# phase_sense.net
KiCad netlist of a schematic drawn in Altium Designer
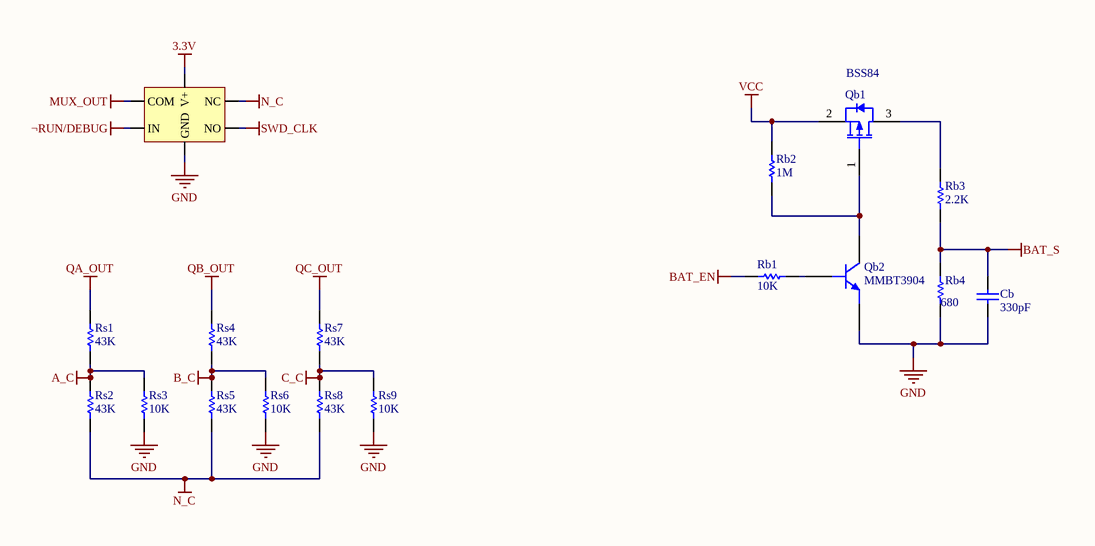
[diagram p0: phase_sense.SchDoc]

(export (version "E")
  (design (tool "Eeschema 10.0.6"))
  (components
    (comp (ref "Cb")
      (value "330pF")
      (footprint "CAPC2012L")
      (description "CAP CER 330PF 100V 5% NP0 0805")
      (fields (field (name "MANUFACTURER PART NUMBER") "CL21C331JCANNNC"))
      (libsource (lib "flxlib") (part "CAP-NO_POL"))
    )
    (comp (ref "MUX")
      (value "TS5A3159A")
      (footprint "JEDEC_MO-178AB")
      (description "IC SWITCH SPDT SOT23-6")
      (fields
        (field (name "MANUFACTURER") "\"Texas Instruments\"")
        (field (name "MANUFACTURER PART NUMBER") "TS5A3159ADBVR")
      )
      (libsource (lib "flxlib") (part "TS5A3159A"))
    )
    (comp (ref "Qb1")
      (value "BSS84")
      (footprint "SOT23-3L")
      (description "MOSFET P-CH 50V 130MA SOT-23")
      (fields (field (name "MANUFACTURER") "Fairchild Semiconductor"))
      (libsource (lib "flxlib") (part "MOSFET-P-GSD"))
    )
    (comp (ref "Qb2")
      (value "MMBT3904")
      (footprint "SOT23-3L")
      (description "TRANSISTOR NPN 40V 0.2A SOT23")
      (fields (field (name "MANUFACTURER") "NXP Semiconductors") (field (name "Comment") "BJT-NPN-BEC"))
      (libsource (lib "flxlib") (part "BJT-NPN-BEC"))
    )
    (comp (ref "Rb1")
      (value "10K")
      (footprint "RESC1608L")
      (description "RES 10K OHM 1/10W 5% 0603")
      (fields (field (name "MANUFACTURER PART NUMBER") "RC1608J103CS"))
      (libsource (lib "flxlib") (part "RES"))
    )
    (comp (ref "Rb2")
      (value "1M")
      (footprint "RESC1608L")
      (description "RES 1.00M OHM 1/10W 1% 0603 SMD")
      (fields
        (field (name "MANUFACTURER") "Yageo")
        (field (name "MANUFACTURER PART NUMBER") "RC0603FR-071ML")
      )
      (libsource (lib "flxlib") (part "RES"))
    )
    (comp (ref "Rb3")
      (value "2.2K")
      (footprint "RESC1608L")
      (description "RES 2.2K OHM 1/10W 1% 0603 SMD")
      (fields
        (field (name "MANUFACTURER") "Rohm Semiconductor")
        (field (name "MANUFACTURER PART NUMBER") "MCR03ERTF2201")
      )
      (libsource (lib "flxlib") (part "RES"))
    )
    (comp (ref "Rb4")
      (value "680")
      (footprint "RESC1608L")
      (description "RES 680 OHM 1/10W 1% 0603 SMD")
      (fields
        (field (name "MANUFACTURER") "Rohm Semiconductor")
        (field (name "MANUFACTURER PART NUMBER") "MCR03ERTF6800")
      )
      (libsource (lib "flxlib") (part "RES"))
    )
    (comp (ref "Rs1")
      (value "43K")
      (footprint "RESC1608L")
      (description "RES 10K OHM 1/10W 5% 0603")
      (fields (field (name "MANUFACTURER PART NUMBER") "RC1608J103CS"))
      (libsource (lib "flxlib") (part "RES"))
    )
    (comp (ref "Rs2")
      (value "43K")
      (footprint "RESC1608L")
      (description "RES 10K OHM 1/10W 5% 0603")
      (fields (field (name "MANUFACTURER PART NUMBER") "RC1608J103CS"))
      (libsource (lib "flxlib") (part "RES"))
    )
    (comp (ref "Rs3")
      (value "10K")
      (footprint "RESC1608L")
      (description "RES 10K OHM 1/10W 5% 0603")
      (fields (field (name "MANUFACTURER PART NUMBER") "RC1608J103CS"))
      (libsource (lib "flxlib") (part "RES"))
    )
    (comp (ref "Rs4")
      (value "43K")
      (footprint "RESC1608L")
      (description "RES 10K OHM 1/10W 5% 0603")
      (fields (field (name "MANUFACTURER PART NUMBER") "RC1608J103CS"))
      (libsource (lib "flxlib") (part "RES"))
    )
    (comp (ref "Rs5")
      (value "43K")
      (footprint "RESC1608L")
      (description "RES 10K OHM 1/10W 5% 0603")
      (fields (field (name "MANUFACTURER PART NUMBER") "RC1608J103CS"))
      (libsource (lib "flxlib") (part "RES"))
    )
    (comp (ref "Rs6")
      (value "10K")
      (footprint "RESC1608L")
      (description "RES 10K OHM 1/10W 5% 0603")
      (fields (field (name "MANUFACTURER PART NUMBER") "RC1608J103CS"))
      (libsource (lib "flxlib") (part "RES"))
    )
    (comp (ref "Rs7")
      (value "43K")
      (footprint "RESC1608L")
      (description "RES 10K OHM 1/10W 5% 0603")
      (fields (field (name "MANUFACTURER PART NUMBER") "RC1608J103CS"))
      (libsource (lib "flxlib") (part "RES"))
    )
    (comp (ref "Rs8")
      (value "43K")
      (footprint "RESC1608L")
      (description "RES 10K OHM 1/10W 5% 0603")
      (fields (field (name "MANUFACTURER PART NUMBER") "RC1608J103CS"))
      (libsource (lib "flxlib") (part "RES"))
    )
    (comp (ref "Rs9")
      (value "10K")
      (footprint "RESC1608L")
      (description "RES 10K OHM 1/10W 5% 0603")
      (fields (field (name "MANUFACTURER PART NUMBER") "RC1608J103CS"))
      (libsource (lib "flxlib") (part "RES"))
    )
  )
  (nets
    (net (code "1") (name "3.3V") (class "Default")
      (node (ref "MUX") (pin "5") (pinfunction "V+_5") (pintype "passive"))
    )
    (net (code "2") (name "A_C") (class "Default")
      (node (ref "Rs1") (pin "2") (pinfunction "2_2") (pintype "passive"))
      (node (ref "Rs2") (pin "1") (pinfunction "1_1") (pintype "passive"))
      (node (ref "Rs3") (pin "1") (pinfunction "1_1") (pintype "passive"))
    )
    (net (code "3") (name "BAT_EN") (class "Default")
      (node (ref "Rb1") (pin "2") (pinfunction "2_2") (pintype "passive"))
    )
    (net (code "4") (name "BAT_S") (class "Default")
      (node (ref "Cb") (pin "1") (pinfunction "1_1") (pintype "passive"))
      (node (ref "Rb3") (pin "2") (pinfunction "2_2") (pintype "passive"))
      (node (ref "Rb4") (pin "1") (pinfunction "1_1") (pintype "passive"))
    )
    (net (code "5") (name "B_C") (class "Default")
      (node (ref "Rs4") (pin "2") (pinfunction "2_2") (pintype "passive"))
      (node (ref "Rs5") (pin "1") (pinfunction "1_1") (pintype "passive"))
      (node (ref "Rs6") (pin "1") (pinfunction "1_1") (pintype "passive"))
    )
    (net (code "6") (name "C_C") (class "Default")
      (node (ref "Rs7") (pin "2") (pinfunction "2_2") (pintype "passive"))
      (node (ref "Rs8") (pin "1") (pinfunction "1_1") (pintype "passive"))
      (node (ref "Rs9") (pin "1") (pinfunction "1_1") (pintype "passive"))
    )
    (net (code "7") (name "GND") (class "Default")
      (node (ref "Cb") (pin "2") (pinfunction "2_2") (pintype "passive"))
      (node (ref "MUX") (pin "2") (pinfunction "GND_2") (pintype "passive"))
      (node (ref "Qb2") (pin "2") (pinfunction "E_2") (pintype "passive"))
      (node (ref "Rb4") (pin "2") (pinfunction "2_2") (pintype "passive"))
      (node (ref "Rs3") (pin "2") (pinfunction "2_2") (pintype "passive"))
      (node (ref "Rs6") (pin "2") (pinfunction "2_2") (pintype "passive"))
      (node (ref "Rs9") (pin "2") (pinfunction "2_2") (pintype "passive"))
    )
    (net (code "8") (name "MUX_OUT") (class "Default")
      (node (ref "MUX") (pin "4") (pinfunction "COM_4") (pintype "passive"))
    )
    (net (code "9") (name "N_C") (class "Default")
      (node (ref "MUX") (pin "3") (pinfunction "NC_3") (pintype "passive"))
      (node (ref "Rs2") (pin "2") (pinfunction "2_2") (pintype "passive"))
      (node (ref "Rs5") (pin "2") (pinfunction "2_2") (pintype "passive"))
      (node (ref "Rs8") (pin "2") (pinfunction "2_2") (pintype "passive"))
    )
    (net (code "10") (name "Net-(Qb1-D)") (class "Default")
      (node (ref "Qb1") (pin "3") (pinfunction "D_3") (pintype "passive"))
      (node (ref "Rb3") (pin "1") (pinfunction "1_1") (pintype "passive"))
    )
    (net (code "11") (name "Net-(Qb1-G)") (class "Default")
      (node (ref "Qb1") (pin "1") (pinfunction "G_1") (pintype "passive"))
      (node (ref "Qb2") (pin "3") (pinfunction "C_3") (pintype "passive"))
      (node (ref "Rb2") (pin "2") (pinfunction "2_2") (pintype "passive"))
    )
    (net (code "12") (name "Net-(Qb2-B)") (class "Default")
      (node (ref "Qb2") (pin "1") (pinfunction "B_1") (pintype "passive"))
      (node (ref "Rb1") (pin "1") (pinfunction "1_1") (pintype "passive"))
    )
    (net (code "13") (name "QA_OUT") (class "Default")
      (node (ref "Rs1") (pin "1") (pinfunction "1_1") (pintype "passive"))
    )
    (net (code "14") (name "QB_OUT") (class "Default")
      (node (ref "Rs4") (pin "1") (pinfunction "1_1") (pintype "passive"))
    )
    (net (code "15") (name "QC_OUT") (class "Default")
      (node (ref "Rs7") (pin "1") (pinfunction "1_1") (pintype "passive"))
    )
    (net (code "16") (name "SWD_CLK") (class "Default")
      (node (ref "MUX") (pin "1") (pinfunction "NO_1") (pintype "passive"))
    )
    (net (code "17") (name "VCC") (class "Default")
      (node (ref "Qb1") (pin "2") (pinfunction "S_2") (pintype "passive"))
      (node (ref "Rb2") (pin "1") (pinfunction "1_1") (pintype "passive"))
    )
    (net (code "18") (name "¬RUN{slash}DEBUG") (class "Default")
      (node (ref "MUX") (pin "6") (pinfunction "IN_6") (pintype "passive"))
    )
  )
)
